# AC_Line_detection.net
KiCad netlist of a schematic drawn in EAGLE
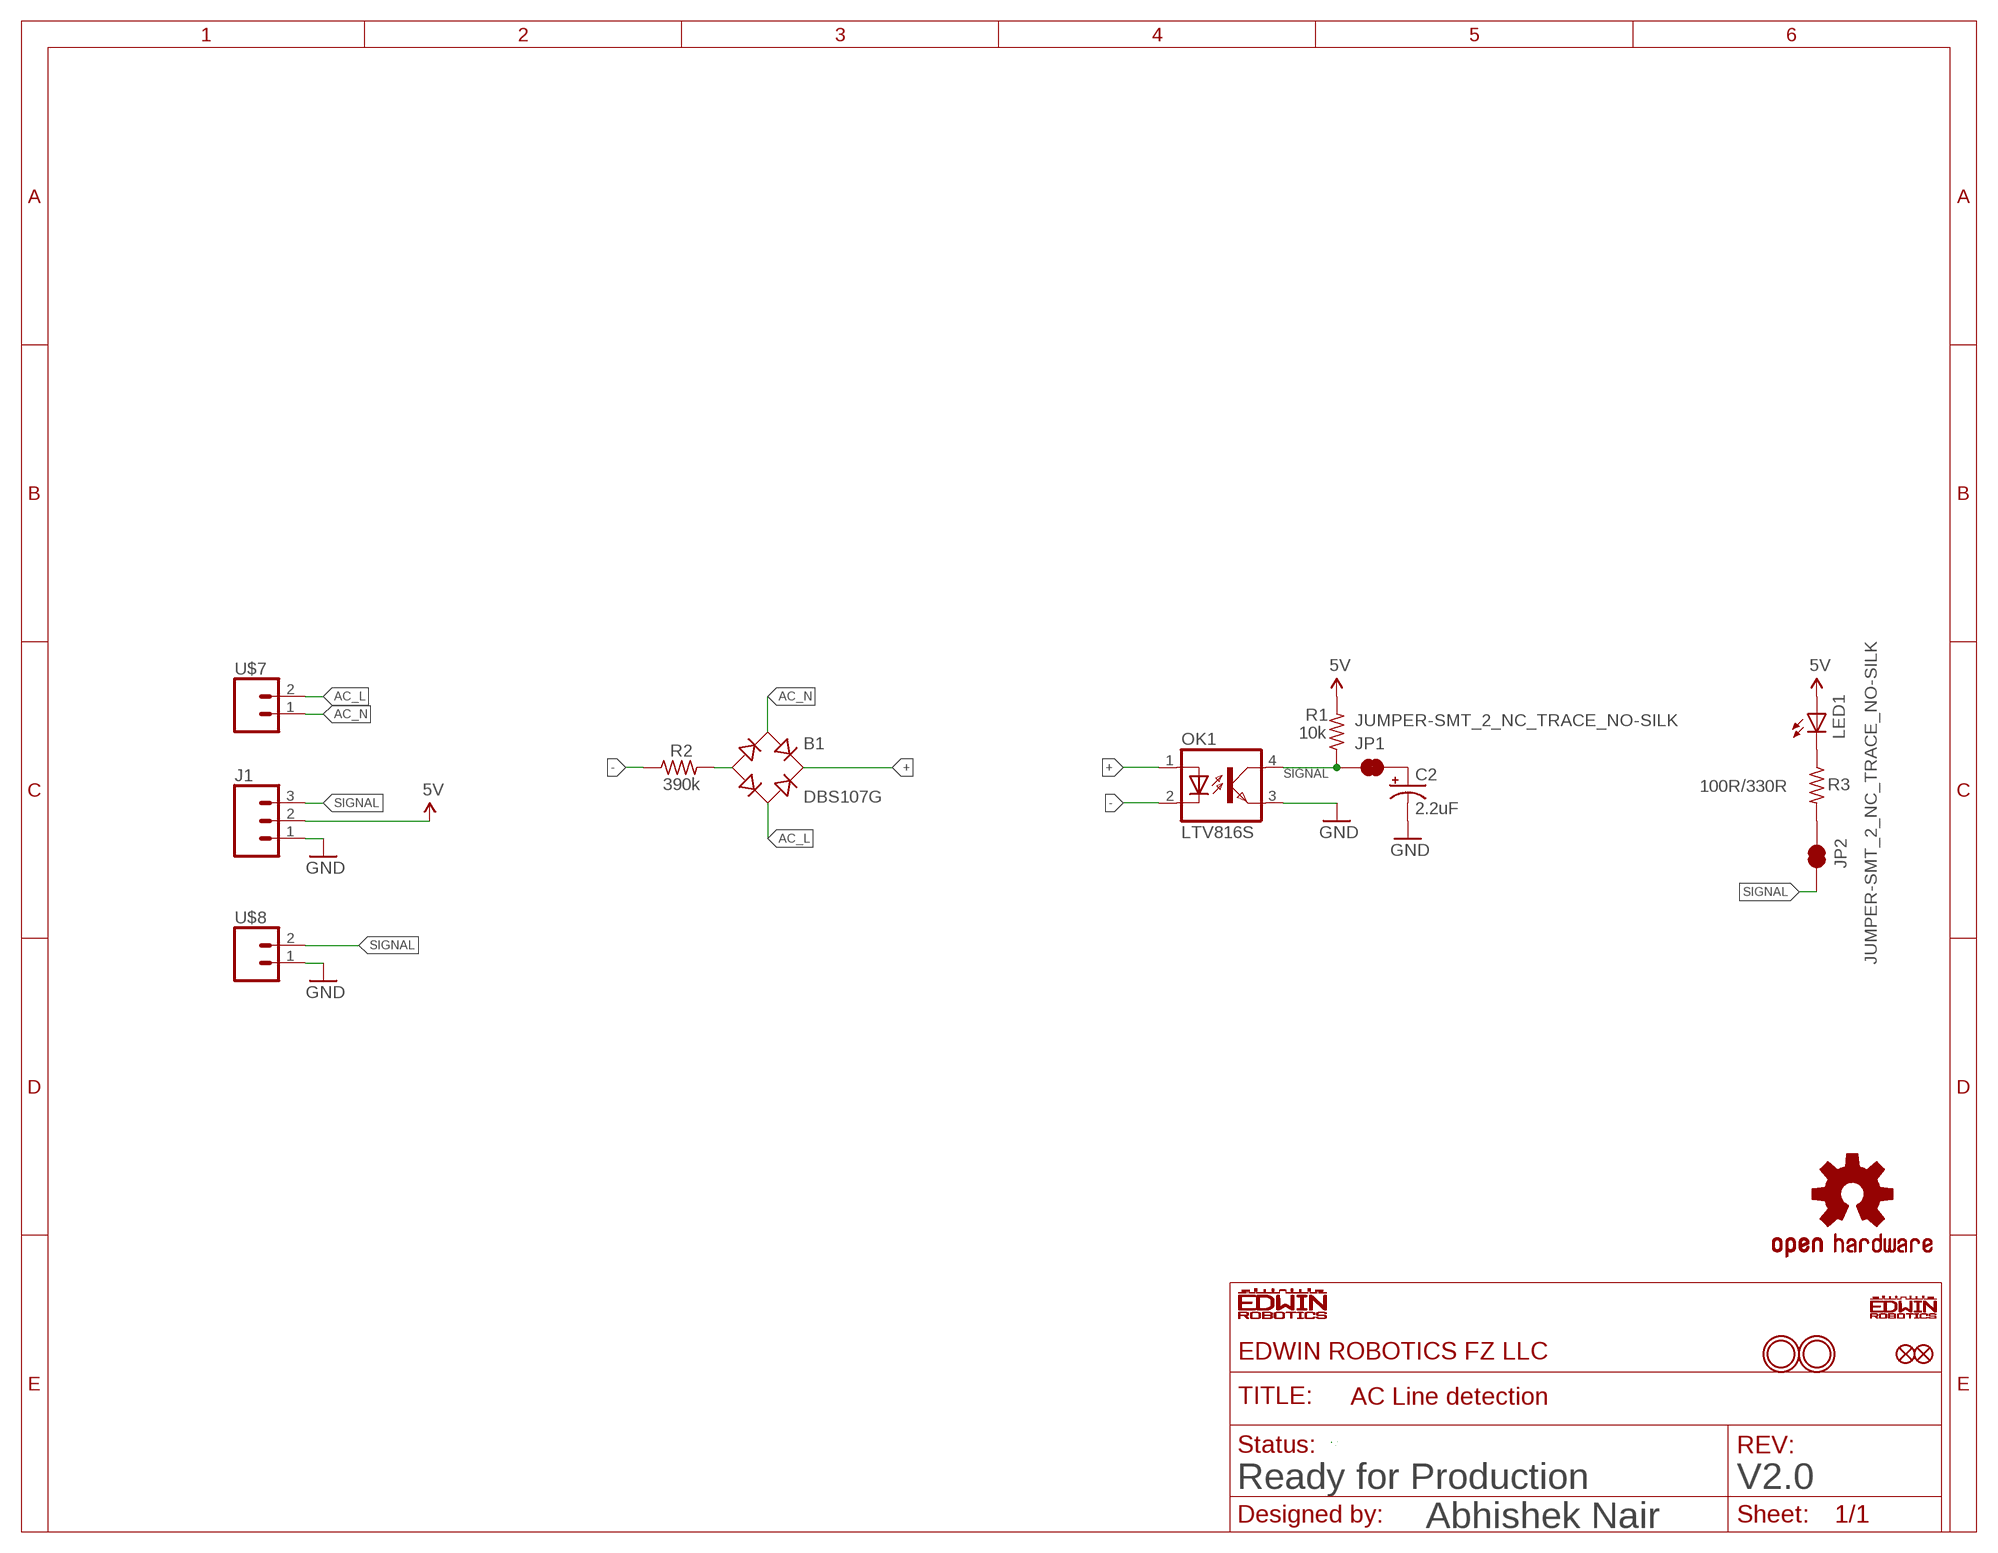
[diagram p0: schematic, sheet 1]

(export (version "E")
  (design (tool "Eeschema 10.0.6"))
  (components
    (comp (ref "B1")
      (value "DBS107G")
      (footprint "eagle-import:DBS")
      (libsource (lib "eagle-import") (part "DB?GS107"))
    )
    (comp (ref "C2")
      (value "2.2uF")
      (footprint "eagle-import:CAPACITOR-2.2UF_4X5MM_JENNY")
      (libsource (lib "eagle-import") (part "CPOL-USCAP-4X5MM"))
    )
    (comp (ref "FID1")
      (value "FIDUCIAL\"\"")
      (footprint "eagle-import:FIDUCIAL_1MM")
      (libsource (lib "eagle-import") (part "FIDUCIAL{dblquote}{dblquote}"))
    )
    (comp (ref "FID2")
      (value "FIDUCIAL\"\"")
      (footprint "eagle-import:FIDUCIAL_1MM")
      (libsource (lib "eagle-import") (part "FIDUCIAL{dblquote}{dblquote}"))
    )
    (comp (ref "J1")
      (value "CONN_03")
      (footprint "eagle-import:1X03")
      (libsource (lib "eagle-import") (part "CONN_03"))
    )
    (comp (ref "JP1")
      (value "JUMPER-SMT_2_NC_TRACE_NO-SILK")
      (footprint "eagle-import:SMT-JUMPER_2_NC_TRACE_NO-SILK")
      (libsource (lib "eagle-import") (part "JUMPER-SMT_2_NC_TRACE_NO-SILK"))
    )
    (comp (ref "JP2")
      (value "JUMPER-SMT_2_NC_TRACE_NO-SILK")
      (footprint "eagle-import:SMT-JUMPER_2_NC_TRACE_NO-SILK")
      (libsource (lib "eagle-import") (part "JUMPER-SMT_2_NC_TRACE_NO-SILK"))
    )
    (comp (ref "LED1")
      (value "LED_TH/SMDCHIPLED_0603")
      (footprint "eagle-import:CHIPLED_0603")
      (libsource (lib "eagle-import") (part "LED_TH/SMDCHIPLED_0603"))
    )
    (comp (ref "LOGO1")
      (value "OSHW-LOGOMINI")
      (footprint "eagle-import:OSHW-LOGO-MINI")
      (libsource (lib "eagle-import") (part "OSHW-LOGOMINI"))
    )
    (comp (ref "OK1")
      (value "LTV816S")
      (footprint "eagle-import:DIL4-SMD")
      (libsource (lib "eagle-import") (part "LTV816S"))
    )
    (comp (ref "R1")
      (value "10k")
      (footprint "eagle-import:R0603")
      (libsource (lib "eagle-import") (part "R-US_R0603"))
    )
    (comp (ref "R2")
      (value "390k")
      (footprint "eagle-import:R0603")
      (libsource (lib "eagle-import") (part "R-US_R0603"))
    )
    (comp (ref "R3")
      (value "100R/330R")
      (footprint "eagle-import:R0603")
      (libsource (lib "eagle-import") (part "R-US_R0603"))
    )
    (comp (ref "U$1")
      (value "LOGO-9.5MMX4.5MM")
      (footprint "eagle-import:LOGO-9.5MMX4.5MM")
      (libsource (lib "eagle-import") (part "LOGO-9.5MMX4.5MM"))
    )
    (comp (ref "U$5")
      (value "MOUNTINGHOLE3.0THIN")
      (footprint "eagle-import:MOUNTINGHOLE_3.0_PLATEDTHIN")
      (libsource (lib "eagle-import") (part "MOUNTINGHOLE3.0THIN"))
    )
    (comp (ref "U$6")
      (value "MOUNTINGHOLE3.0THIN")
      (footprint "eagle-import:MOUNTINGHOLE_3.0_PLATEDTHIN")
      (libsource (lib "eagle-import") (part "MOUNTINGHOLE3.0THIN"))
    )
    (comp (ref "U$7")
      (value "SCREW_TERMINALS-2P-5MM")
      (footprint "eagle-import:W237-102")
      (libsource (lib "eagle-import") (part "SCREW_TERMINALS-2P-5MM"))
    )
    (comp (ref "U$8")
      (value "SCREW_TERMINALS-2P-5MM")
      (footprint "eagle-import:W237-102")
      (libsource (lib "eagle-import") (part "SCREW_TERMINALS-2P-5MM"))
    )
  )
  (nets
    (net (code "1") (name "+") (class "Default")
      (node (ref "B1") (pin "+") (pinfunction "+_+") (pintype "passive"))
      (node (ref "OK1") (pin "1") (pinfunction "A_1") (pintype "passive"))
    )
    (net (code "2") (name "-") (class "Default")
      (node (ref "OK1") (pin "2") (pinfunction "C_2") (pintype "passive"))
      (node (ref "R2") (pin "1") (pinfunction "1_1") (pintype "passive"))
    )
    (net (code "3") (name "5V") (class "Default")
      (node (ref "J1") (pin "2") (pinfunction "2_2") (pintype "passive"))
      (node (ref "LED1") (pin "A") (pinfunction "A_A") (pintype "passive"))
      (node (ref "R1") (pin "2") (pinfunction "2_2") (pintype "passive"))
    )
    (net (code "4") (name "AC_L") (class "Default")
      (node (ref "B1") (pin "AC2") (pinfunction "AC2_AC2") (pintype "passive"))
      (node (ref "U$7") (pin "2") (pinfunction "2_2") (pintype "passive"))
    )
    (net (code "5") (name "AC_N") (class "Default")
      (node (ref "B1") (pin "AC1") (pinfunction "AC1_AC1") (pintype "passive"))
      (node (ref "U$7") (pin "1") (pinfunction "1_1") (pintype "passive"))
    )
    (net (code "6") (name "GND") (class "Default")
      (node (ref "C2") (pin "-") (pinfunction "-_-") (pintype "passive"))
      (node (ref "J1") (pin "1") (pinfunction "1_1") (pintype "passive"))
      (node (ref "OK1") (pin "3") (pinfunction "EMIT_3") (pintype "passive"))
      (node (ref "U$8") (pin "1") (pinfunction "1_1") (pintype "passive"))
    )
    (net (code "7") (name "Net-(B1-Pad-)") (class "Default")
      (node (ref "B1") (pin "-") (pinfunction "-_-") (pintype "passive"))
      (node (ref "R2") (pin "2") (pinfunction "2_2") (pintype "passive"))
    )
    (net (code "8") (name "Net-(C2-Pad+)") (class "Default")
      (node (ref "C2") (pin "+") (pinfunction "+_+") (pintype "passive"))
      (node (ref "JP1") (pin "2") (pinfunction "2_2") (pintype "passive"))
    )
    (net (code "9") (name "Net-(JP2-Pad1)") (class "Default")
      (node (ref "JP2") (pin "1") (pinfunction "1_1") (pintype "passive"))
      (node (ref "R3") (pin "2") (pinfunction "2_2") (pintype "passive"))
    )
    (net (code "10") (name "Net-(LED1-PadC)") (class "Default")
      (node (ref "LED1") (pin "C") (pinfunction "C_C") (pintype "passive"))
      (node (ref "R3") (pin "1") (pinfunction "1_1") (pintype "passive"))
    )
    (net (code "11") (name "SIGNAL") (class "Default")
      (node (ref "J1") (pin "3") (pinfunction "3_3") (pintype "passive"))
      (node (ref "JP1") (pin "1") (pinfunction "1_1") (pintype "passive"))
      (node (ref "JP2") (pin "2") (pinfunction "2_2") (pintype "passive"))
      (node (ref "OK1") (pin "4") (pinfunction "COL_4") (pintype "passive"))
      (node (ref "R1") (pin "1") (pinfunction "1_1") (pintype "passive"))
      (node (ref "U$8") (pin "2") (pinfunction "2_2") (pintype "passive"))
    )
  )
)
